# Sheet4.net
KiCad netlist of a schematic drawn in Altium Designer
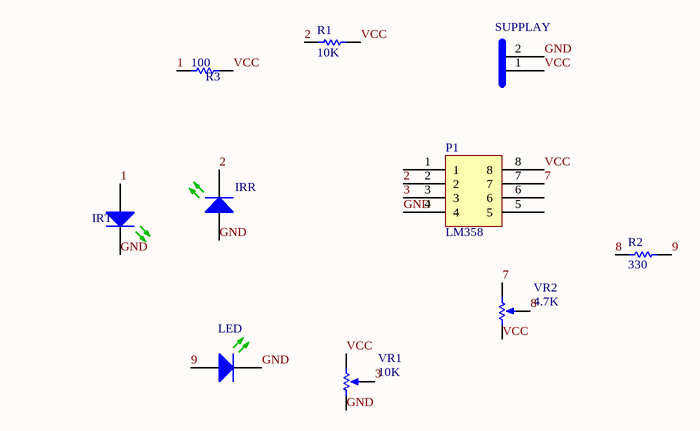
[diagram p0: Sheet4.SchDoc]

(export (version "E")
  (design (tool "Eeschema 10.0.6"))
  (components
    (comp (ref "IRR")
      (value "~")
      (footprint "LED-GREEN")
      (description "Typical RED GaAs LED")
      (fields (field (name "PUBLISHER") "Altium Limited"))
      (libsource (lib "Devindia_v4.0") (part "LED-GREEN"))
    )
    (comp (ref "IRT")
      (value "~")
      (footprint "LED-GREEN")
      (description "Typical RED GaAs LED")
      (fields (field (name "PUBLISHER") "Altium Limited"))
      (libsource (lib "Devindia_v4.0") (part "LED-GREEN"))
    )
    (comp (ref "LED")
      (value "~")
      (footprint "LED-GREEN")
      (description "Typical RED GaAs LED")
      (fields (field (name "PUBLISHER") "Altium Limited"))
      (libsource (lib "Devindia_v4.0") (part "LED-GREEN"))
    )
    (comp (ref "P1")
      (value "LM358")
      (footprint "dip-8pin")
      (libsource (lib "Devindia_v4.0") (part "ATML 911 240C04PU27"))
    )
    (comp (ref "R1")
      (value "10K")
      (footprint "res- 2.54x3")
      (libsource (lib "Devindia_v2.0") (part "Resistor 2.54x3"))
    )
    (comp (ref "R2")
      (value "330")
      (footprint "res- 2.54x3")
      (libsource (lib "Devindia_v2.0") (part "Resistor 2.54x3"))
    )
    (comp (ref "R3")
      (value "100")
      (footprint "res- 2.54x3")
      (libsource (lib "Devindia_v2.0") (part "Resistor 2.54x3"))
    )
    (comp (ref "SUPPLAY")
      (value "~")
      (footprint "bergstrip-2pin")
      (libsource (lib "Devindia_v4.0") (part "BURG STRIP 2"))
    )
    (comp (ref "VR1")
      (value "10K")
      (footprint "reg-variable")
      (libsource (lib "Devindia_v4.0") (part "Variable Resistor"))
    )
    (comp (ref "VR2")
      (value "4.7K")
      (footprint "reg-variable")
      (libsource (lib "Devindia_v4.0") (part "Variable Resistor"))
    )
  )
  (nets
    (net (code "1") (name "/1") (class "Default")
      (node (ref "IRT") (pin "1") (pinfunction "A_1") (pintype "passive"))
      (node (ref "R3") (pin "1") (pinfunction "1_1") (pintype "passive"))
    )
    (net (code "2") (name "/2") (class "Default")
      (node (ref "IRR") (pin "2") (pinfunction "K_2") (pintype "passive"))
      (node (ref "P1") (pin "2") (pinfunction "2_2") (pintype "passive"))
      (node (ref "R1") (pin "1") (pinfunction "1_1") (pintype "passive"))
    )
    (net (code "3") (name "/3") (class "Default")
      (node (ref "P1") (pin "3") (pinfunction "3_3") (pintype "passive"))
      (node (ref "VR1") (pin "2") (pinfunction "TAP_2") (pintype "passive"))
    )
    (net (code "4") (name "/7") (class "Default")
      (node (ref "P1") (pin "7") (pinfunction "7_7") (pintype "passive"))
      (node (ref "VR2") (pin "3") (pinfunction "BOT_3") (pintype "passive"))
    )
    (net (code "5") (name "/8") (class "Default")
      (node (ref "R2") (pin "1") (pinfunction "1_1") (pintype "passive"))
      (node (ref "VR2") (pin "2") (pinfunction "TAP_2") (pintype "passive"))
    )
    (net (code "6") (name "/9") (class "Default")
      (node (ref "LED") (pin "1") (pinfunction "A_1") (pintype "passive"))
      (node (ref "R2") (pin "2") (pinfunction "2_2") (pintype "passive"))
    )
    (net (code "7") (name "/GND") (class "Default")
      (node (ref "IRR") (pin "1") (pinfunction "A_1") (pintype "passive"))
      (node (ref "IRT") (pin "2") (pinfunction "K_2") (pintype "passive"))
      (node (ref "LED") (pin "2") (pinfunction "K_2") (pintype "passive"))
      (node (ref "P1") (pin "4") (pinfunction "4_4") (pintype "passive"))
      (node (ref "SUPPLAY") (pin "2") (pinfunction "2_2") (pintype "passive"))
      (node (ref "VR1") (pin "1") (pinfunction "TOP_1") (pintype "passive"))
    )
    (net (code "8") (name "/VCC") (class "Default")
      (node (ref "P1") (pin "8") (pinfunction "8_8") (pintype "passive"))
      (node (ref "R1") (pin "2") (pinfunction "2_2") (pintype "passive"))
      (node (ref "R3") (pin "2") (pinfunction "2_2") (pintype "passive"))
      (node (ref "SUPPLAY") (pin "1") (pinfunction "1_1") (pintype "passive"))
      (node (ref "VR1") (pin "3") (pinfunction "BOT_3") (pintype "passive"))
      (node (ref "VR2") (pin "1") (pinfunction "TOP_1") (pintype "passive"))
    )
    (net (code "9") (name "unconnected-(P1-Pad1)") (class "Default")
      (node (ref "P1") (pin "1") (pinfunction "1_1") (pintype "passive"))
    )
    (net (code "10") (name "unconnected-(P1-Pad5)") (class "Default")
      (node (ref "P1") (pin "5") (pinfunction "5_5") (pintype "passive"))
    )
    (net (code "11") (name "unconnected-(P1-Pad6)") (class "Default")
      (node (ref "P1") (pin "6") (pinfunction "6_6") (pintype "passive"))
    )
  )
)
